# sensors.net
KiCad netlist of a schematic drawn in Altium Designer
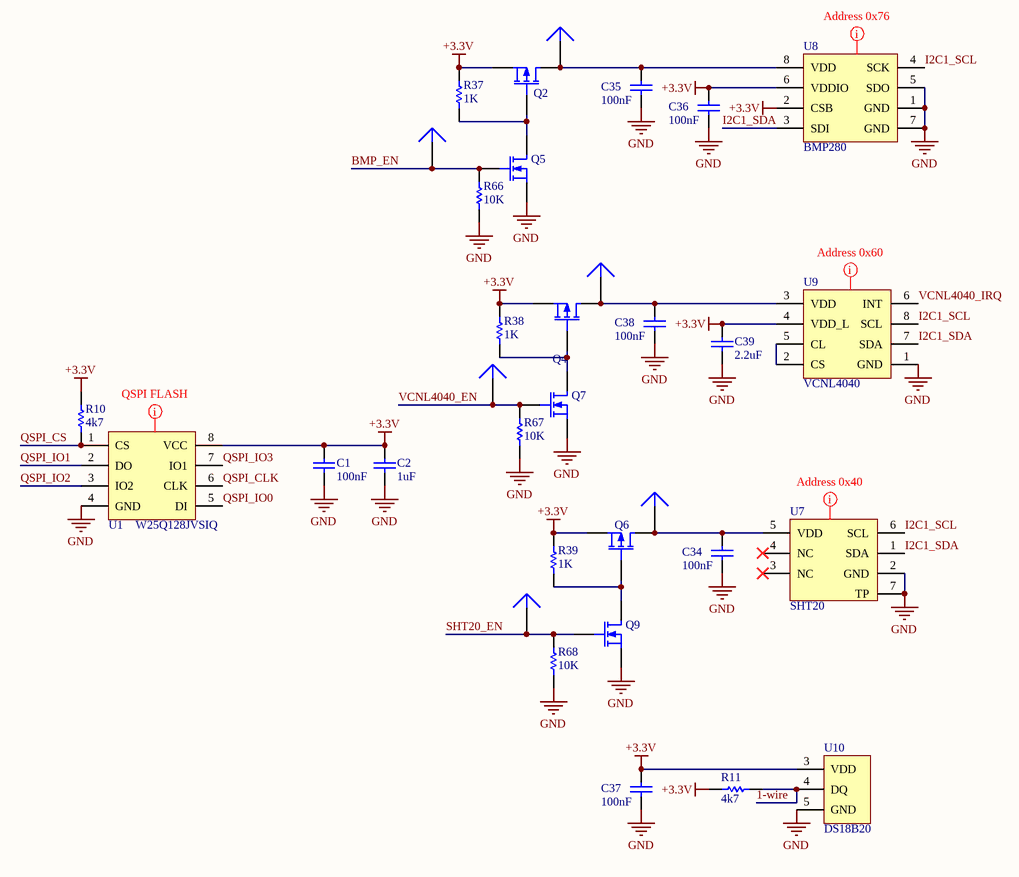
[diagram p0: sensors.SchDoc]

(export (version "E")
  (design (tool "Eeschema 10.0.6"))
  (components
    (comp (ref "C1")
      (value "100nF")
      (footprint "C0402")
      (description "Capacitor")
      (fields (field (name "Comment") "Cap 100nF"))
      (libsource (lib "integratedLib") (part "Cap 100nF"))
    )
    (comp (ref "C2")
      (value "1uF")
      (footprint "C0402")
      (description "Capacitor")
      (fields (field (name "Comment") "Cap 1uF"))
      (libsource (lib "integratedLib") (part "Cap 1uF"))
    )
    (comp (ref "C34")
      (value "100nF")
      (footprint "C0402")
      (description "Capacitor")
      (fields (field (name "Comment") "Cap 100nF"))
      (libsource (lib "integratedLib") (part "Cap 100nF"))
    )
    (comp (ref "C35")
      (value "100nF")
      (footprint "C0402")
      (description "Capacitor")
      (fields (field (name "Comment") "Cap 100nF"))
      (libsource (lib "integratedLib") (part "Cap 100nF"))
    )
    (comp (ref "C36")
      (value "100nF")
      (footprint "C0402")
      (description "Capacitor")
      (fields (field (name "Comment") "Cap 100nF"))
      (libsource (lib "integratedLib") (part "Cap 100nF"))
    )
    (comp (ref "C37")
      (value "100nF")
      (footprint "C0402")
      (description "Capacitor")
      (fields (field (name "Comment") "Cap 100nF"))
      (libsource (lib "integratedLib") (part "Cap 100nF"))
    )
    (comp (ref "C38")
      (value "100nF")
      (footprint "C0402")
      (description "Capacitor")
      (fields (field (name "Comment") "Cap 100nF"))
      (libsource (lib "integratedLib") (part "Cap 100nF"))
    )
    (comp (ref "C39")
      (value "2.2uF")
      (footprint "C0402")
      (description "Capacitor")
      (fields (field (name "Comment") "Cap 2.2uF"))
      (libsource (lib "integratedLib") (part "Cap 2.2uF"))
    )
    (comp (ref "P20")
      (value "Plug")
      (footprint "pin smd")
      (fields (field (name "PUBLISHER") "Altium Limited"))
      (libsource (lib "integratedLib") (part "Plug"))
    )
    (comp (ref "P21")
      (value "Plug")
      (footprint "pin smd")
      (fields (field (name "PUBLISHER") "Altium Limited"))
      (libsource (lib "integratedLib") (part "Plug"))
    )
    (comp (ref "P22")
      (value "Plug")
      (footprint "pin smd")
      (fields (field (name "PUBLISHER") "Altium Limited"))
      (libsource (lib "integratedLib") (part "Plug"))
    )
    (comp (ref "P26")
      (value "Plug")
      (footprint "pin smd")
      (fields (field (name "PUBLISHER") "Altium Limited"))
      (libsource (lib "integratedLib") (part "Plug"))
    )
    (comp (ref "P27")
      (value "Plug")
      (footprint "pin smd")
      (fields (field (name "PUBLISHER") "Altium Limited"))
      (libsource (lib "integratedLib") (part "Plug"))
    )
    (comp (ref "P28")
      (value "Plug")
      (footprint "pin smd")
      (fields (field (name "PUBLISHER") "Altium Limited"))
      (libsource (lib "integratedLib") (part "Plug"))
    )
    (comp (ref "Q2")
      (value "AO3401A")
      (footprint "SOT23")
      (description "P-Channel MOSFET AO3401A")
      (fields (field (name "PUBLISHER") "Altium Limited"))
      (libsource (lib "integratedLib") (part "MOSFET-P"))
    )
    (comp (ref "Q4")
      (value "AO3401A")
      (footprint "SOT23")
      (description "P-Channel MOSFET AO3401A")
      (fields (field (name "PUBLISHER") "Altium Limited"))
      (libsource (lib "integratedLib") (part "MOSFET-P"))
    )
    (comp (ref "Q5")
      (value "AO3400A")
      (footprint "SOT23")
      (description "N-MOSFET AO3400A")
      (fields (field (name "PUBLISHER") "Altium Limited"))
      (libsource (lib "integratedLib") (part "MOSFET-N"))
    )
    (comp (ref "Q6")
      (value "AO3401A")
      (footprint "SOT23")
      (description "P-Channel MOSFET AO3401A")
      (fields (field (name "PUBLISHER") "Altium Limited"))
      (libsource (lib "integratedLib") (part "MOSFET-P"))
    )
    (comp (ref "Q7")
      (value "AO3400A")
      (footprint "SOT23")
      (description "N-MOSFET AO3400A")
      (fields (field (name "PUBLISHER") "Altium Limited"))
      (libsource (lib "integratedLib") (part "MOSFET-N"))
    )
    (comp (ref "Q9")
      (value "AO3400A")
      (footprint "SOT23")
      (description "N-MOSFET AO3400A")
      (fields (field (name "PUBLISHER") "Altium Limited"))
      (libsource (lib "integratedLib") (part "MOSFET-N"))
    )
    (comp (ref "R10")
      (value "4k7")
      (footprint "R0402")
      (description "Resistor")
      (fields (field (name "Comment") "Res_4k7"))
      (libsource (lib "integratedLib") (part "Res_4k7"))
    )
    (comp (ref "R11")
      (value "4k7")
      (footprint "R0402")
      (description "Resistor")
      (fields (field (name "Comment") "Res_4k7"))
      (libsource (lib "integratedLib") (part "Res_4k7"))
    )
    (comp (ref "R37")
      (value "1K")
      (footprint "R0402")
      (description "Resistor")
      (fields (field (name "Comment") "Res_1K"))
      (libsource (lib "integratedLib") (part "Res_1K"))
    )
    (comp (ref "R38")
      (value "1K")
      (footprint "R0402")
      (description "Resistor")
      (fields (field (name "Comment") "Res_1K"))
      (libsource (lib "integratedLib") (part "Res_1K"))
    )
    (comp (ref "R39")
      (value "1K")
      (footprint "R0402")
      (description "Resistor")
      (fields (field (name "Comment") "Res_1K"))
      (libsource (lib "integratedLib") (part "Res_1K"))
    )
    (comp (ref "R66")
      (value "10K")
      (footprint "R0402")
      (description "Resistor")
      (fields (field (name "Comment") "Res_10K"))
      (libsource (lib "integratedLib") (part "Res_10K"))
    )
    (comp (ref "R67")
      (value "10K")
      (footprint "R0402")
      (description "Resistor")
      (fields (field (name "Comment") "Res_10K"))
      (libsource (lib "integratedLib") (part "Res_10K"))
    )
    (comp (ref "R68")
      (value "10K")
      (footprint "R0402")
      (description "Resistor")
      (fields (field (name "Comment") "Res_10K"))
      (libsource (lib "integratedLib") (part "Res_10K"))
    )
    (comp (ref "U1")
      (value "W25Q128JVSIQ")
      (footprint "SOIC8_208-mil")
      (description "SPI Flash  memory 128MB")
      (libsource (lib "integratedLib") (part "flash_memory"))
    )
    (comp (ref "U7")
      (value "SHT20")
      (footprint "DFN6")
      (description "Humidity and Temperature SensorIC")
      (libsource (lib "integratedLib") (part "SHT20"))
    )
    (comp (ref "U8")
      (value "BMP280")
      (footprint "LGA8")
      (description "Digital Pressure Sensor")
      (libsource (lib "integratedLib") (part "BMP280"))
    )
    (comp (ref "U9")
      (value "VCNL4040")
      (footprint "VCNL4040M3OE")
      (libsource (lib "integratedLib") (part "VCNL4040"))
    )
    (comp (ref "U10")
      (value "DS18B20")
      (footprint "SO8")
      (fields (field (name "PUBLISHER") "Altium Limited"))
      (libsource (lib "integratedLib") (part "DS18B20"))
    )
  )
  (nets
    (net (code "1") (name "+3.3V") (class "Default")
      (node (ref "C1") (pin "2") (pinfunction "2_2") (pintype "passive"))
      (node (ref "C2") (pin "2") (pinfunction "2_2") (pintype "passive"))
      (node (ref "C36") (pin "2") (pinfunction "2_2") (pintype "passive"))
      (node (ref "C37") (pin "2") (pinfunction "2_2") (pintype "passive"))
      (node (ref "C39") (pin "2") (pinfunction "2_2") (pintype "passive"))
      (node (ref "Q2") (pin "2") (pinfunction "S_2") (pintype "passive"))
      (node (ref "Q4") (pin "2") (pinfunction "S_2") (pintype "passive"))
      (node (ref "Q6") (pin "2") (pinfunction "S_2") (pintype "passive"))
      (node (ref "R10") (pin "2") (pinfunction "2_2") (pintype "passive"))
      (node (ref "R11") (pin "1") (pinfunction "1_1") (pintype "passive"))
      (node (ref "R37") (pin "2") (pinfunction "2_2") (pintype "passive"))
      (node (ref "R38") (pin "2") (pinfunction "2_2") (pintype "passive"))
      (node (ref "R39") (pin "2") (pinfunction "2_2") (pintype "passive"))
      (node (ref "U1") (pin "8") (pinfunction "VCC_8") (pintype "passive"))
      (node (ref "U10") (pin "3") (pinfunction "VDD_3") (pintype "passive"))
      (node (ref "U8") (pin "2") (pinfunction "CSB_2") (pintype "power_in"))
      (node (ref "U8") (pin "6") (pinfunction "VDDIO_6") (pintype "power_in"))
      (node (ref "U9") (pin "4") (pinfunction "VDD_L_4") (pintype "passive"))
    )
    (net (code "2") (name "/1-wire") (class "Default")
      (node (ref "R11") (pin "2") (pinfunction "2_2") (pintype "passive"))
      (node (ref "U10") (pin "4") (pinfunction "DQ_4") (pintype "passive"))
    )
    (net (code "3") (name "/BMP_EN") (class "Default")
      (node (ref "P26") (pin "1") (pinfunction "1_1") (pintype "passive"))
      (node (ref "Q5") (pin "1") (pinfunction "G_1") (pintype "passive"))
      (node (ref "R66") (pin "2") (pinfunction "2_2") (pintype "passive"))
    )
    (net (code "4") (name "/I2C1_SCL") (class "Default")
      (node (ref "U7") (pin "6") (pinfunction "SCL_6") (pintype "power_in"))
      (node (ref "U8") (pin "4") (pinfunction "SCK_4") (pintype "passive"))
      (node (ref "U9") (pin "8") (pinfunction "SCL_8") (pintype "passive"))
    )
    (net (code "5") (name "/I2C1_SDA") (class "Default")
      (node (ref "U7") (pin "1") (pinfunction "SDA_1") (pintype "power_in"))
      (node (ref "U8") (pin "3") (pinfunction "SDI_3") (pintype "passive"))
      (node (ref "U9") (pin "7") (pinfunction "SDA_7") (pintype "passive"))
    )
    (net (code "6") (name "/QSPI_CLK") (class "Default")
      (node (ref "U1") (pin "6") (pinfunction "CLK_6") (pintype "passive"))
    )
    (net (code "7") (name "/QSPI_CS") (class "Default")
      (node (ref "R10") (pin "1") (pinfunction "1_1") (pintype "passive"))
      (node (ref "U1") (pin "1") (pinfunction "CS_1") (pintype "passive"))
    )
    (net (code "8") (name "/QSPI_IO0") (class "Default")
      (node (ref "U1") (pin "5") (pinfunction "DI_5") (pintype "passive"))
    )
    (net (code "9") (name "/QSPI_IO1") (class "Default")
      (node (ref "U1") (pin "2") (pinfunction "DO_2") (pintype "passive"))
    )
    (net (code "10") (name "/QSPI_IO2") (class "Default")
      (node (ref "U1") (pin "3") (pinfunction "IO2_3") (pintype "passive"))
    )
    (net (code "11") (name "/QSPI_IO3") (class "Default")
      (node (ref "U1") (pin "7") (pinfunction "IO1_7") (pintype "passive"))
    )
    (net (code "12") (name "/SHT20_EN") (class "Default")
      (node (ref "P28") (pin "1") (pinfunction "1_1") (pintype "passive"))
      (node (ref "Q9") (pin "1") (pinfunction "G_1") (pintype "passive"))
      (node (ref "R68") (pin "2") (pinfunction "2_2") (pintype "passive"))
    )
    (net (code "13") (name "/VCNL4040_EN") (class "Default")
      (node (ref "P27") (pin "1") (pinfunction "1_1") (pintype "passive"))
      (node (ref "Q7") (pin "1") (pinfunction "G_1") (pintype "passive"))
      (node (ref "R67") (pin "2") (pinfunction "2_2") (pintype "passive"))
    )
    (net (code "14") (name "/VCNL4040_IRQ") (class "Default")
      (node (ref "U9") (pin "6") (pinfunction "INT_6") (pintype "power_in"))
    )
    (net (code "15") (name "GND") (class "Default")
      (node (ref "C1") (pin "1") (pinfunction "1_1") (pintype "passive"))
      (node (ref "C2") (pin "1") (pinfunction "1_1") (pintype "passive"))
      (node (ref "C34") (pin "1") (pinfunction "1_1") (pintype "passive"))
      (node (ref "C35") (pin "1") (pinfunction "1_1") (pintype "passive"))
      (node (ref "C36") (pin "1") (pinfunction "1_1") (pintype "passive"))
      (node (ref "C37") (pin "1") (pinfunction "1_1") (pintype "passive"))
      (node (ref "C38") (pin "1") (pinfunction "1_1") (pintype "passive"))
      (node (ref "C39") (pin "1") (pinfunction "1_1") (pintype "passive"))
      (node (ref "Q5") (pin "2") (pinfunction "S_2") (pintype "passive"))
      (node (ref "Q7") (pin "2") (pinfunction "S_2") (pintype "passive"))
      (node (ref "Q9") (pin "2") (pinfunction "S_2") (pintype "passive"))
      (node (ref "R66") (pin "1") (pinfunction "1_1") (pintype "passive"))
      (node (ref "R67") (pin "1") (pinfunction "1_1") (pintype "passive"))
      (node (ref "R68") (pin "1") (pinfunction "1_1") (pintype "passive"))
      (node (ref "U1") (pin "4") (pinfunction "GND_4") (pintype "passive"))
      (node (ref "U10") (pin "5") (pinfunction "GND_5") (pintype "passive"))
      (node (ref "U7") (pin "2") (pinfunction "GND_2") (pintype "power_in"))
      (node (ref "U7") (pin "7") (pinfunction "TP_7") (pintype "power_in"))
      (node (ref "U8") (pin "1") (pinfunction "GND_1") (pintype "power_in"))
      (node (ref "U8") (pin "5") (pinfunction "SDO_5") (pintype "power_in"))
      (node (ref "U8") (pin "7") (pinfunction "GND_7") (pintype "passive"))
      (node (ref "U9") (pin "1") (pinfunction "GND_1") (pintype "power_in"))
    )
    (net (code "16") (name "Net-(Q2-D)") (class "Default")
      (node (ref "C35") (pin "2") (pinfunction "2_2") (pintype "passive"))
      (node (ref "P20") (pin "1") (pinfunction "1_1") (pintype "passive"))
      (node (ref "Q2") (pin "3") (pinfunction "D_3") (pintype "passive"))
      (node (ref "U8") (pin "8") (pinfunction "VDD_8") (pintype "passive"))
    )
    (net (code "17") (name "Net-(Q2-G)") (class "Default")
      (node (ref "Q2") (pin "1") (pinfunction "G_1") (pintype "passive"))
      (node (ref "Q5") (pin "3") (pinfunction "D_3") (pintype "passive"))
      (node (ref "R37") (pin "1") (pinfunction "1_1") (pintype "passive"))
    )
    (net (code "18") (name "Net-(Q4-D)") (class "Default")
      (node (ref "C38") (pin "2") (pinfunction "2_2") (pintype "passive"))
      (node (ref "P21") (pin "1") (pinfunction "1_1") (pintype "passive"))
      (node (ref "Q4") (pin "3") (pinfunction "D_3") (pintype "passive"))
      (node (ref "U9") (pin "3") (pinfunction "VDD_3") (pintype "passive"))
    )
    (net (code "19") (name "Net-(Q4-G)") (class "Default")
      (node (ref "Q4") (pin "1") (pinfunction "G_1") (pintype "passive"))
      (node (ref "Q7") (pin "3") (pinfunction "D_3") (pintype "passive"))
      (node (ref "R38") (pin "1") (pinfunction "1_1") (pintype "passive"))
    )
    (net (code "20") (name "Net-(Q6-D)") (class "Default")
      (node (ref "C34") (pin "2") (pinfunction "2_2") (pintype "passive"))
      (node (ref "P22") (pin "1") (pinfunction "1_1") (pintype "passive"))
      (node (ref "Q6") (pin "3") (pinfunction "D_3") (pintype "passive"))
      (node (ref "U7") (pin "5") (pinfunction "VDD_5") (pintype "passive"))
    )
    (net (code "21") (name "Net-(Q6-G)") (class "Default")
      (node (ref "Q6") (pin "1") (pinfunction "G_1") (pintype "passive"))
      (node (ref "Q9") (pin "3") (pinfunction "D_3") (pintype "passive"))
      (node (ref "R39") (pin "1") (pinfunction "1_1") (pintype "passive"))
    )
    (net (code "22") (name "Net-(U9-CL)") (class "Default")
      (node (ref "U9") (pin "2") (pinfunction "CS_2") (pintype "power_in"))
      (node (ref "U9") (pin "5") (pinfunction "CL_5") (pintype "power_in"))
    )
    (net (code "23") (name "unconnected-(U7-NC-Pad3)") (class "Default")
      (node (ref "U7") (pin "3") (pinfunction "NC_3") (pintype "passive+no_connect"))
    )
    (net (code "24") (name "unconnected-(U7-NC-Pad4)") (class "Default")
      (node (ref "U7") (pin "4") (pinfunction "NC_4") (pintype "power_in+no_connect"))
    )
  )
)
